# Dual_ESC_6-24V_3_6A_V3_Easy_EDA.net
KiCad netlist of a schematic drawn in EasyEDA Pro
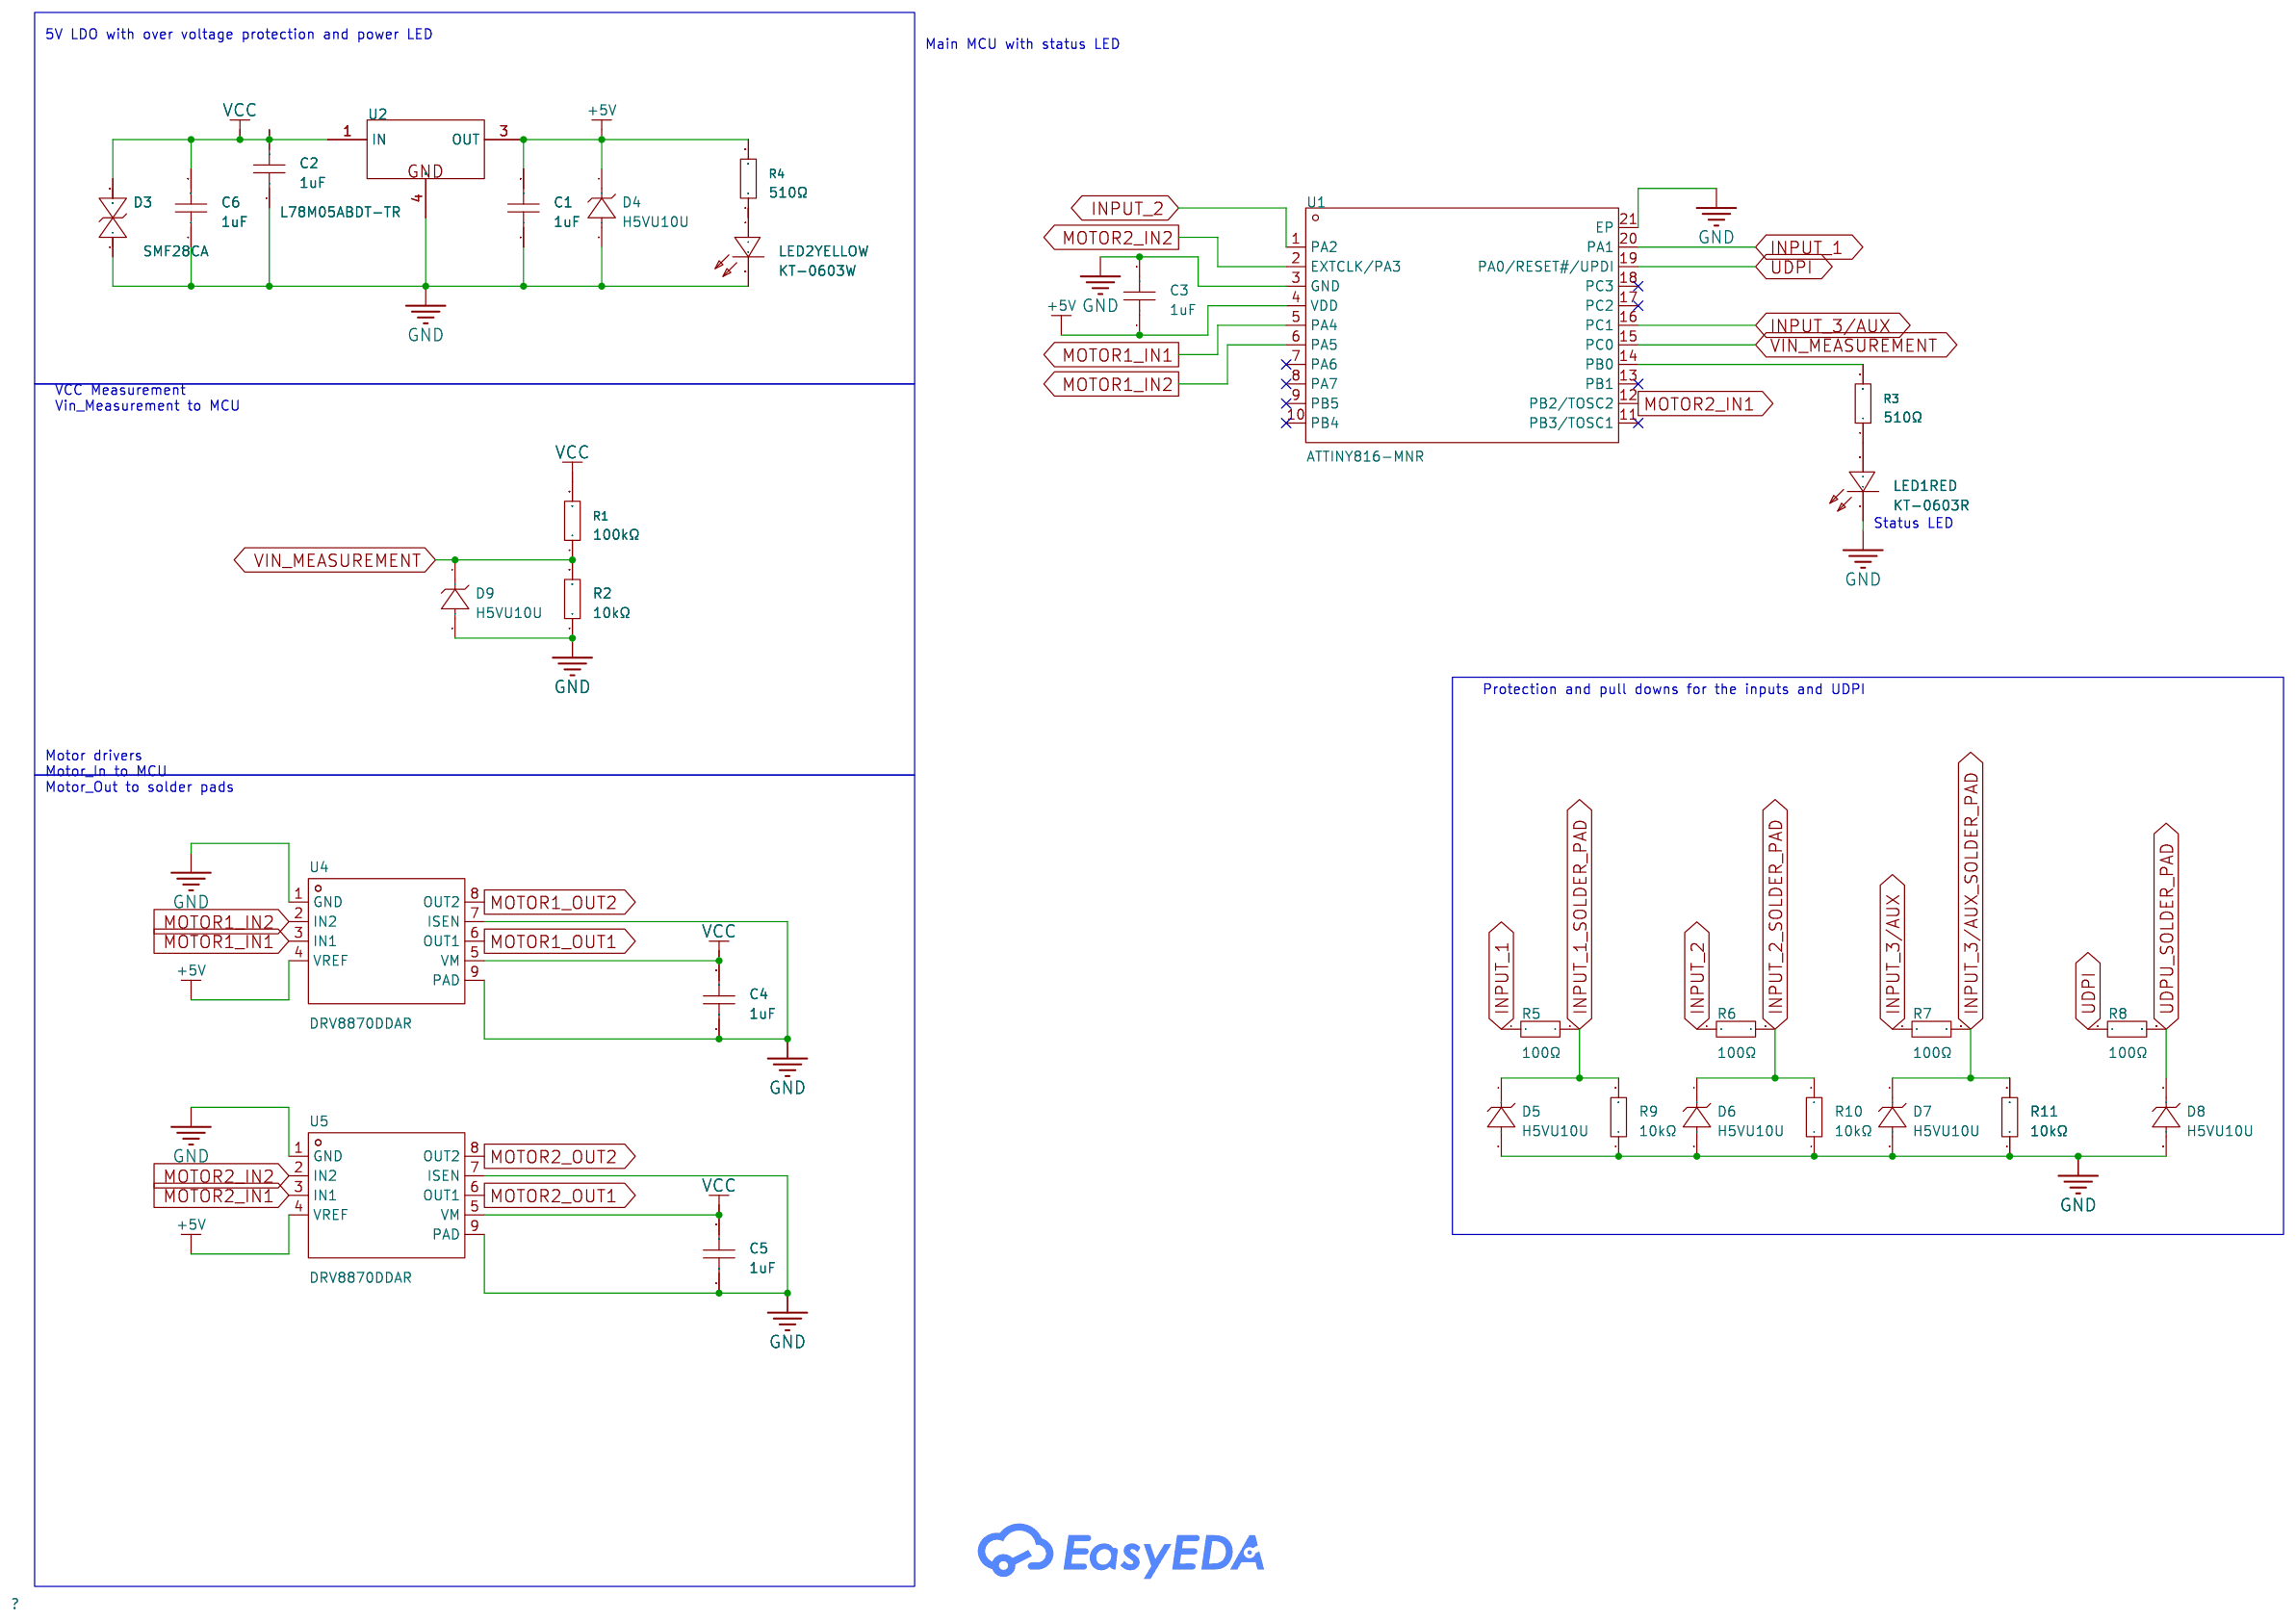
[diagram p0: schematic sheet]

(export (version "E")
  (design (tool "Eeschema 10.0.6"))
  (components
    (comp (ref "C1")
      (value "1uF")
      (footprint "easyedapro:C0402")
      (description "Capacitance:1uF Tolerance:±10% Tolerance:±10% Voltage Rating:25V Temperature Coefficient:X5R")
      (fields
        (field (name "Manufacturer Part") "CL05A105KA5NQNC")
        (field (name "Manufacturer") "SAMSUNG(三星)")
      )
      (libsource (lib "easyedapro") (part "CL05A105KA5NQNC"))
    )
    (comp (ref "C2")
      (value "1uF")
      (footprint "easyedapro:C0603")
      (description "Capacitance:1uF Tolerance:±10% Tolerance:±10% Voltage Rating:50V Temperature Coefficient:X5R")
      (fields
        (field (name "Manufacturer Part") "CL10A105KB8NNNC")
        (field (name "Manufacturer") "SAMSUNG(三星)")
      )
      (libsource (lib "easyedapro") (part "CL10A105KB8NNNC"))
    )
    (comp (ref "C3")
      (value "1uF")
      (footprint "easyedapro:C0402")
      (description "Capacitance:1uF Tolerance:±10% Tolerance:±10% Voltage Rating:25V Temperature Coefficient:X5R")
      (fields
        (field (name "Manufacturer Part") "CL05A105KA5NQNC")
        (field (name "Manufacturer") "SAMSUNG(三星)")
      )
      (libsource (lib "easyedapro") (part "CL05A105KA5NQNC"))
    )
    (comp (ref "C4")
      (value "1uF")
      (footprint "easyedapro:C0603")
      (description "Capacitance:1uF Tolerance:±10% Tolerance:±10% Voltage Rating:50V Temperature Coefficient:X5R")
      (fields
        (field (name "Manufacturer Part") "CL10A105KB8NNNC")
        (field (name "Manufacturer") "SAMSUNG(三星)")
      )
      (libsource (lib "easyedapro") (part "CL10A105KB8NNNC"))
    )
    (comp (ref "C5")
      (value "1uF")
      (footprint "easyedapro:C0603")
      (description "Capacitance:1uF Tolerance:±10% Tolerance:±10% Voltage Rating:50V Temperature Coefficient:X5R")
      (fields
        (field (name "Manufacturer Part") "CL10A105KB8NNNC")
        (field (name "Manufacturer") "SAMSUNG(三星)")
      )
      (libsource (lib "easyedapro") (part "CL10A105KB8NNNC"))
    )
    (comp (ref "C6")
      (value "1uF")
      (footprint "easyedapro:C0603")
      (description "Capacitance:1uF Tolerance:±10% Tolerance:±10% Voltage Rating:50V Temperature Coefficient:X5R")
      (fields
        (field (name "Manufacturer Part") "CL10A105KB8NNNC")
        (field (name "Manufacturer") "SAMSUNG(三星)")
      )
      (libsource (lib "easyedapro") (part "CL10A105KB8NNNC"))
    )
    (comp (ref "D3")
      (value "SMF28CA")
      (footprint "easyedapro:SOD-123FL_L2.7-W1.8-LS3.8-BI")
      (fields (field (name "Manufacturer") "R+O(宏嘉诚)"))
      (libsource (lib "easyedapro") (part "SMF28CA_C19077517"))
    )
    (comp (ref "D4")
      (value "H5VU10U")
      (footprint "easyedapro:DFN1006-2L-RD")
      (fields (field (name "Manufacturer") "R+O(宏嘉诚)"))
      (libsource (lib "easyedapro") (part "H5VU10U"))
    )
    (comp (ref "D5")
      (value "H5VU10U")
      (footprint "easyedapro:DFN1006-2L-RD")
      (fields (field (name "Manufacturer") "R+O(宏嘉诚)"))
      (libsource (lib "easyedapro") (part "H5VU10U"))
    )
    (comp (ref "D6")
      (value "H5VU10U")
      (footprint "easyedapro:DFN1006-2L-RD")
      (fields (field (name "Manufacturer") "R+O(宏嘉诚)"))
      (libsource (lib "easyedapro") (part "H5VU10U"))
    )
    (comp (ref "D7")
      (value "H5VU10U")
      (footprint "easyedapro:DFN1006-2L-RD")
      (fields (field (name "Manufacturer") "R+O(宏嘉诚)"))
      (libsource (lib "easyedapro") (part "H5VU10U"))
    )
    (comp (ref "D8")
      (value "H5VU10U")
      (footprint "easyedapro:DFN1006-2L-RD")
      (fields (field (name "Manufacturer") "R+O(宏嘉诚)"))
      (libsource (lib "easyedapro") (part "H5VU10U"))
    )
    (comp (ref "D9")
      (value "H5VU10U")
      (footprint "easyedapro:DFN1006-2L-RD")
      (fields (field (name "Manufacturer") "R+O(宏嘉诚)"))
      (libsource (lib "easyedapro") (part "H5VU10U"))
    )
    (comp (ref "LED1RED")
      (value "KT-0603R")
      (footprint "easyedapro:LED0603-RD")
      (fields (field (name "Manufacturer") "KENTO"))
      (libsource (lib "easyedapro") (part "KT-0603R"))
    )
    (comp (ref "LED2YELLOW")
      (value "KT-0603W")
      (footprint "easyedapro:LED0603-R-RD_WHITE")
      (fields (field (name "Manufacturer") "KENTO"))
      (libsource (lib "easyedapro") (part "0603White light_C2290"))
    )
    (comp (ref "R1")
      (value "100kΩ")
      (footprint "easyedapro:R0402")
      (fields
        (field (name "Manufacturer Part") "0402WGF1003TCE")
        (field (name "Manufacturer") "UNI-ROYAL(厚声)")
      )
      (libsource (lib "easyedapro") (part "0402WGF1003TCE"))
    )
    (comp (ref "R2")
      (value "10kΩ")
      (footprint "easyedapro:R0402")
      (fields
        (field (name "Manufacturer Part") "0402WGF1002TCE")
        (field (name "Manufacturer") "UNI-ROYAL(厚声)")
      )
      (libsource (lib "easyedapro") (part "0402WGF1002TCE"))
    )
    (comp (ref "R3")
      (value "510Ω")
      (footprint "easyedapro:R0402")
      (fields
        (field (name "Manufacturer Part") "0402WGF5100TCE")
        (field (name "Manufacturer") "UNI-ROYAL(厚声)")
      )
      (libsource (lib "easyedapro") (part "0402WGF5100TCE"))
    )
    (comp (ref "R4")
      (value "510Ω")
      (footprint "easyedapro:R0402")
      (fields
        (field (name "Manufacturer Part") "0402WGF5100TCE")
        (field (name "Manufacturer") "UNI-ROYAL(厚声)")
      )
      (libsource (lib "easyedapro") (part "0402WGF5100TCE"))
    )
    (comp (ref "R5")
      (value "100Ω")
      (footprint "easyedapro:R0402")
      (fields
        (field (name "Manufacturer Part") "0402WGF1000TCE")
        (field (name "Manufacturer") "UNI-ROYAL(厚声)")
      )
      (libsource (lib "easyedapro") (part "0402WGF1000TCE"))
    )
    (comp (ref "R6")
      (value "100Ω")
      (footprint "easyedapro:R0402")
      (fields
        (field (name "Manufacturer Part") "0402WGF1000TCE")
        (field (name "Manufacturer") "UNI-ROYAL(厚声)")
      )
      (libsource (lib "easyedapro") (part "0402WGF1000TCE"))
    )
    (comp (ref "R7")
      (value "100Ω")
      (footprint "easyedapro:R0402")
      (fields
        (field (name "Manufacturer Part") "0402WGF1000TCE")
        (field (name "Manufacturer") "UNI-ROYAL(厚声)")
      )
      (libsource (lib "easyedapro") (part "0402WGF1000TCE"))
    )
    (comp (ref "R8")
      (value "100Ω")
      (footprint "easyedapro:R0402")
      (fields
        (field (name "Manufacturer Part") "0402WGF1000TCE")
        (field (name "Manufacturer") "UNI-ROYAL(厚声)")
      )
      (libsource (lib "easyedapro") (part "0402WGF1000TCE"))
    )
    (comp (ref "R9")
      (value "10kΩ")
      (footprint "easyedapro:R0402")
      (fields
        (field (name "Manufacturer Part") "0402WGF1002TCE")
        (field (name "Manufacturer") "UNI-ROYAL(厚声)")
      )
      (libsource (lib "easyedapro") (part "0402WGF1002TCE"))
    )
    (comp (ref "R10")
      (value "10kΩ")
      (footprint "easyedapro:R0402")
      (fields
        (field (name "Manufacturer Part") "0402WGF1002TCE")
        (field (name "Manufacturer") "UNI-ROYAL(厚声)")
      )
      (libsource (lib "easyedapro") (part "0402WGF1002TCE"))
    )
    (comp (ref "R11")
      (value "10kΩ")
      (footprint "easyedapro:R0402")
      (fields
        (field (name "Manufacturer Part") "0402WGF1002TCE")
        (field (name "Manufacturer") "UNI-ROYAL(厚声)")
      )
      (libsource (lib "easyedapro") (part "0402WGF1002TCE"))
    )
    (comp (ref "U1")
      (value "ATTINY816-MNR")
      (fields (field (name "Manufacturer") "MICROCHIP(美国微芯)"))
      (libsource (lib "easyedapro") (part "ATTINY1616-MNR"))
    )
    (comp (ref "U2")
      (value "L78M05ABDT-TR")
      (footprint "easyedapro:TO-252-2_L6.5-W6.1-P4.58-LS10.0-TL")
      (fields (field (name "Manufacturer") "ST(意法半导体)"))
      (libsource (lib "easyedapro") (part "L78M05ABDT-TR"))
    )
    (comp (ref "U4")
      (value "DRV8870DDAR")
      (footprint "easyedapro:HSOP-8_L5.0-W4.0-P1.27-LS6.2-BL-EP")
      (fields (field (name "Manufacturer") "TI(德州仪器)"))
      (libsource (lib "easyedapro") (part "DRV8870DDAR"))
    )
    (comp (ref "U5")
      (value "DRV8870DDAR")
      (footprint "easyedapro:HSOP-8_L5.0-W4.0-P1.27-LS6.2-BL-EP")
      (fields (field (name "Manufacturer") "TI(德州仪器)"))
      (libsource (lib "easyedapro") (part "DRV8870DDAR"))
    )
  )
  (nets
    (net (code "1") (name "+5V") (class "Default")
      (node (ref "C1") (pin "2") (pinfunction "2_2") (pintype "unspecified"))
      (node (ref "C3") (pin "1") (pinfunction "1_1") (pintype "unspecified"))
      (node (ref "D4") (pin "1") (pinfunction "K_1") (pintype "unspecified"))
      (node (ref "R4") (pin "2") (pinfunction "2_2") (pintype "input"))
      (node (ref "U1") (pin "4") (pinfunction "VDD_4") (pintype "unspecified"))
      (node (ref "U2") (pin "3") (pinfunction "OUT_3") (pintype "unspecified"))
      (node (ref "U4") (pin "4") (pinfunction "VREF_4") (pintype "unspecified"))
      (node (ref "U5") (pin "4") (pinfunction "VREF_4") (pintype "unspecified"))
    )
    (net (code "2") (name "GND") (class "Default")
      (node (ref "C1") (pin "1") (pinfunction "1_1") (pintype "unspecified"))
      (node (ref "C2") (pin "1") (pinfunction "1_1") (pintype "unspecified"))
      (node (ref "C3") (pin "2") (pinfunction "2_2") (pintype "unspecified"))
      (node (ref "C4") (pin "1") (pinfunction "1_1") (pintype "unspecified"))
      (node (ref "C5") (pin "1") (pinfunction "1_1") (pintype "unspecified"))
      (node (ref "C6") (pin "1") (pinfunction "1_1") (pintype "unspecified"))
      (node (ref "D3") (pin "1") (pinfunction "1_1") (pintype "unspecified"))
      (node (ref "D4") (pin "2") (pinfunction "A_2") (pintype "unspecified"))
      (node (ref "D5") (pin "2") (pinfunction "A_2") (pintype "unspecified"))
      (node (ref "D6") (pin "2") (pinfunction "A_2") (pintype "unspecified"))
      (node (ref "D7") (pin "2") (pinfunction "A_2") (pintype "unspecified"))
      (node (ref "D8") (pin "2") (pinfunction "A_2") (pintype "unspecified"))
      (node (ref "D9") (pin "2") (pinfunction "A_2") (pintype "unspecified"))
      (node (ref "LED1RED") (pin "1") (pinfunction "K_1") (pintype "unspecified"))
      (node (ref "LED2YELLOW") (pin "2") (pinfunction "K_2") (pintype "unspecified"))
      (node (ref "R10") (pin "1") (pinfunction "1_1") (pintype "input"))
      (node (ref "R11") (pin "1") (pinfunction "1_1") (pintype "input"))
      (node (ref "R2") (pin "1") (pinfunction "1_1") (pintype "input"))
      (node (ref "R9") (pin "1") (pinfunction "1_1") (pintype "input"))
      (node (ref "U1") (pin "21") (pinfunction "EP_21") (pintype "unspecified"))
      (node (ref "U1") (pin "3") (pinfunction "GND_3") (pintype "unspecified"))
      (node (ref "U2") (pin "4") (pinfunction "GND_4") (pintype "unspecified"))
      (node (ref "U4") (pin "1") (pinfunction "GND_1") (pintype "unspecified"))
      (node (ref "U4") (pin "7") (pinfunction "ISEN_7") (pintype "unspecified"))
      (node (ref "U4") (pin "9") (pinfunction "PAD_9") (pintype "unspecified"))
      (node (ref "U5") (pin "1") (pinfunction "GND_1") (pintype "unspecified"))
      (node (ref "U5") (pin "7") (pinfunction "ISEN_7") (pintype "unspecified"))
      (node (ref "U5") (pin "9") (pinfunction "PAD_9") (pintype "unspecified"))
    )
    (net (code "3") (name "INPUT_1") (class "Default")
      (node (ref "R5") (pin "1") (pinfunction "1_1") (pintype "input"))
      (node (ref "U1") (pin "20") (pinfunction "PA1_20") (pintype "unspecified"))
    )
    (net (code "4") (name "INPUT_1_SOLDER_PAD") (class "Default")
      (node (ref "D5") (pin "1") (pinfunction "K_1") (pintype "unspecified"))
      (node (ref "R5") (pin "2") (pinfunction "2_2") (pintype "input"))
      (node (ref "R9") (pin "2") (pinfunction "2_2") (pintype "input"))
    )
    (net (code "5") (name "INPUT_2") (class "Default")
      (node (ref "R6") (pin "1") (pinfunction "1_1") (pintype "input"))
      (node (ref "U1") (pin "1") (pinfunction "PA2_1") (pintype "unspecified"))
    )
    (net (code "6") (name "INPUT_2_SOLDER_PAD") (class "Default")
      (node (ref "D6") (pin "1") (pinfunction "K_1") (pintype "unspecified"))
      (node (ref "R10") (pin "2") (pinfunction "2_2") (pintype "input"))
      (node (ref "R6") (pin "2") (pinfunction "2_2") (pintype "input"))
    )
    (net (code "7") (name "INPUT_3{slash}AUX") (class "Default")
      (node (ref "R7") (pin "1") (pinfunction "1_1") (pintype "input"))
      (node (ref "U1") (pin "16") (pinfunction "PC1_16") (pintype "unspecified"))
    )
    (net (code "8") (name "INPUT_3{slash}AUX_SOLDER_PAD") (class "Default")
      (node (ref "D7") (pin "1") (pinfunction "K_1") (pintype "unspecified"))
      (node (ref "R11") (pin "2") (pinfunction "2_2") (pintype "input"))
      (node (ref "R7") (pin "2") (pinfunction "2_2") (pintype "input"))
    )
    (net (code "9") (name "MOTOR1_IN1") (class "Default")
      (node (ref "U1") (pin "5") (pinfunction "PA4_5") (pintype "unspecified"))
      (node (ref "U4") (pin "3") (pinfunction "IN1_3") (pintype "unspecified"))
    )
    (net (code "10") (name "MOTOR1_IN2") (class "Default")
      (node (ref "U1") (pin "6") (pinfunction "PA5_6") (pintype "unspecified"))
      (node (ref "U4") (pin "2") (pinfunction "IN2_2") (pintype "unspecified"))
    )
    (net (code "11") (name "MOTOR1_OUT1") (class "Default")
      (node (ref "U4") (pin "6") (pinfunction "OUT1_6") (pintype "unspecified"))
    )
    (net (code "12") (name "MOTOR1_OUT2") (class "Default")
      (node (ref "U4") (pin "8") (pinfunction "OUT2_8") (pintype "unspecified"))
    )
    (net (code "13") (name "MOTOR2_IN1") (class "Default")
      (node (ref "U1") (pin "12") (pinfunction "PB2/TOSC2_12") (pintype "unspecified"))
      (node (ref "U5") (pin "3") (pinfunction "IN1_3") (pintype "unspecified"))
    )
    (net (code "14") (name "MOTOR2_IN2") (class "Default")
      (node (ref "U1") (pin "2") (pinfunction "EXTCLK/PA3_2") (pintype "unspecified"))
      (node (ref "U5") (pin "2") (pinfunction "IN2_2") (pintype "unspecified"))
    )
    (net (code "15") (name "MOTOR2_OUT1") (class "Default")
      (node (ref "U5") (pin "6") (pinfunction "OUT1_6") (pintype "unspecified"))
    )
    (net (code "16") (name "MOTOR2_OUT2") (class "Default")
      (node (ref "U5") (pin "8") (pinfunction "OUT2_8") (pintype "unspecified"))
    )
    (net (code "17") (name "Net-(LED1RED-A)") (class "Default")
      (node (ref "LED1RED") (pin "2") (pinfunction "A_2") (pintype "unspecified"))
      (node (ref "R3") (pin "1") (pinfunction "1_1") (pintype "input"))
    )
    (net (code "18") (name "Net-(LED2YELLOW-A)") (class "Default")
      (node (ref "LED2YELLOW") (pin "1") (pinfunction "A_1") (pintype "unspecified"))
      (node (ref "R4") (pin "1") (pinfunction "1_1") (pintype "input"))
    )
    (net (code "19") (name "Net-(U1-PB0)") (class "Default")
      (node (ref "R3") (pin "2") (pinfunction "2_2") (pintype "input"))
      (node (ref "U1") (pin "14") (pinfunction "PB0_14") (pintype "unspecified"))
    )
    (net (code "20") (name "UDPI") (class "Default")
      (node (ref "R8") (pin "1") (pinfunction "1_1") (pintype "input"))
      (node (ref "U1") (pin "19") (pinfunction "PA0/RESET#/UPDI_19") (pintype "unspecified"))
    )
    (net (code "21") (name "UDPU_SOLDER_PAD") (class "Default")
      (node (ref "D8") (pin "1") (pinfunction "K_1") (pintype "unspecified"))
      (node (ref "R8") (pin "2") (pinfunction "2_2") (pintype "input"))
    )
    (net (code "22") (name "VCC") (class "Default")
      (node (ref "C2") (pin "2") (pinfunction "2_2") (pintype "unspecified"))
      (node (ref "C4") (pin "2") (pinfunction "2_2") (pintype "unspecified"))
      (node (ref "C5") (pin "2") (pinfunction "2_2") (pintype "unspecified"))
      (node (ref "C6") (pin "2") (pinfunction "2_2") (pintype "unspecified"))
      (node (ref "D3") (pin "2") (pinfunction "2_2") (pintype "unspecified"))
      (node (ref "R1") (pin "2") (pinfunction "2_2") (pintype "input"))
      (node (ref "U2") (pin "1") (pinfunction "IN_1") (pintype "unspecified"))
      (node (ref "U4") (pin "5") (pinfunction "VM_5") (pintype "unspecified"))
      (node (ref "U5") (pin "5") (pinfunction "VM_5") (pintype "unspecified"))
    )
    (net (code "23") (name "VIN_MEASUREMENT") (class "Default")
      (node (ref "D9") (pin "1") (pinfunction "K_1") (pintype "unspecified"))
      (node (ref "R1") (pin "1") (pinfunction "1_1") (pintype "input"))
      (node (ref "R2") (pin "2") (pinfunction "2_2") (pintype "input"))
      (node (ref "U1") (pin "15") (pinfunction "PC0_15") (pintype "unspecified"))
    )
    (net (code "24") (name "unconnected-(U1-PA6-Pad7)") (class "Default")
      (node (ref "U1") (pin "7") (pinfunction "PA6_7") (pintype "unspecified+no_connect"))
    )
    (net (code "25") (name "unconnected-(U1-PA7-Pad8)") (class "Default")
      (node (ref "U1") (pin "8") (pinfunction "PA7_8") (pintype "unspecified+no_connect"))
    )
    (net (code "26") (name "unconnected-(U1-PB1-Pad13)") (class "Default")
      (node (ref "U1") (pin "13") (pinfunction "PB1_13") (pintype "unspecified+no_connect"))
    )
    (net (code "27") (name "unconnected-(U1-PB3{slash}TOSC1-Pad11)") (class "Default")
      (node (ref "U1") (pin "11") (pinfunction "PB3/TOSC1_11") (pintype "unspecified+no_connect"))
    )
    (net (code "28") (name "unconnected-(U1-PB4-Pad10)") (class "Default")
      (node (ref "U1") (pin "10") (pinfunction "PB4_10") (pintype "unspecified+no_connect"))
    )
    (net (code "29") (name "unconnected-(U1-PB5-Pad9)") (class "Default")
      (node (ref "U1") (pin "9") (pinfunction "PB5_9") (pintype "unspecified+no_connect"))
    )
    (net (code "30") (name "unconnected-(U1-PC2-Pad17)") (class "Default")
      (node (ref "U1") (pin "17") (pinfunction "PC2_17") (pintype "unspecified+no_connect"))
    )
    (net (code "31") (name "unconnected-(U1-PC3-Pad18)") (class "Default")
      (node (ref "U1") (pin "18") (pinfunction "PC3_18") (pintype "unspecified+no_connect"))
    )
  )
)
